# Sheet1.net
KiCad netlist of a schematic drawn in Altium Designer
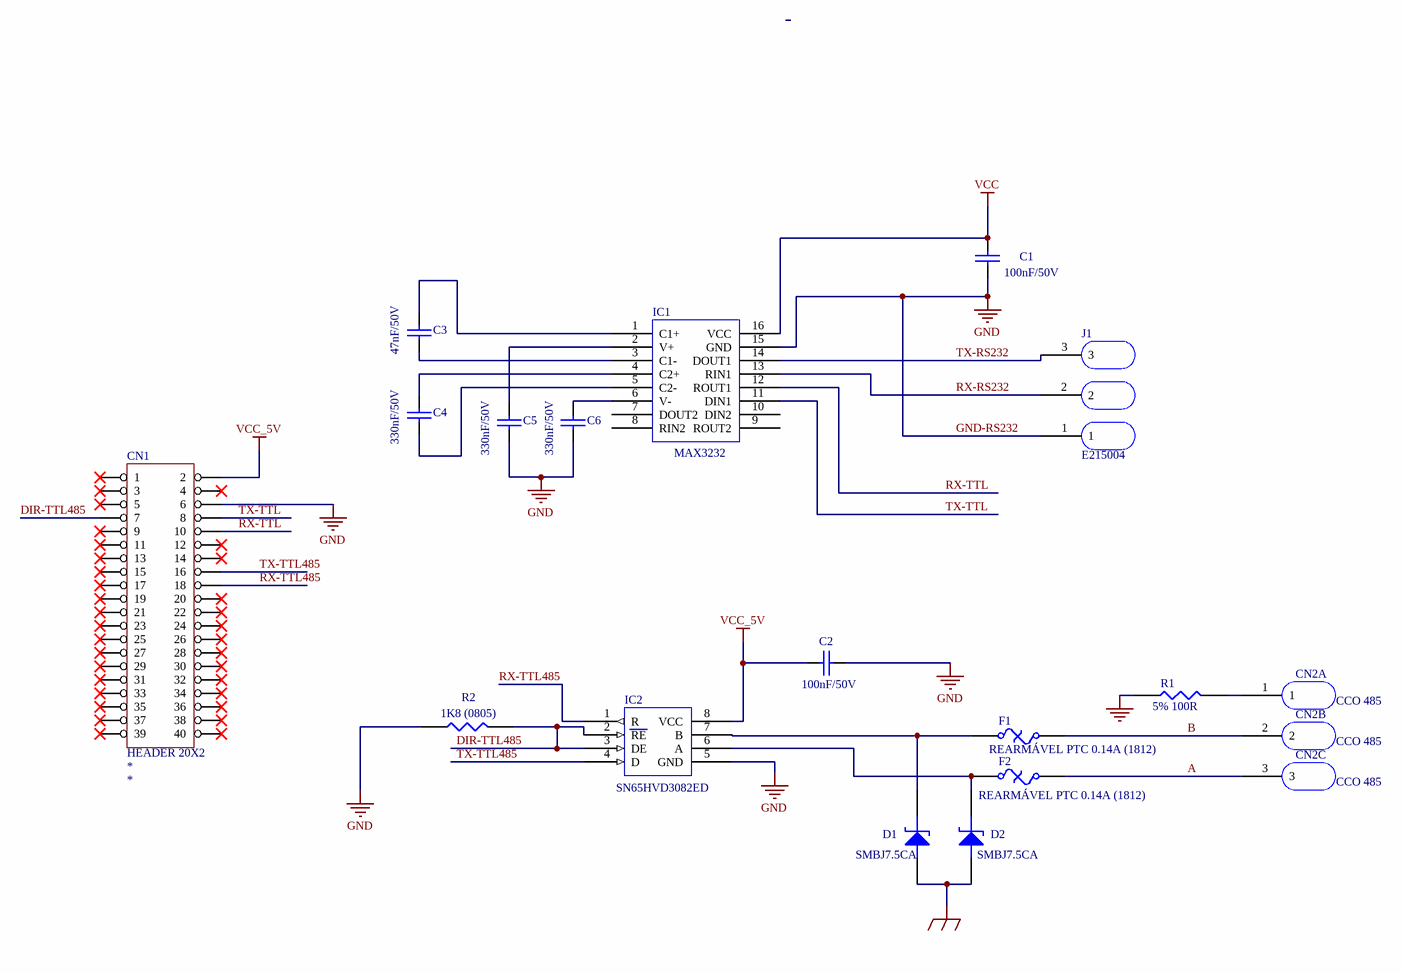
[diagram p0: Sheet1.SchDoc]

(export (version "E")
  (design (tool "Eeschema 10.0.6"))
  (components
    (comp (ref "C1")
      (value "B217602")
      (footprint "C0805")
      (description "COND. CERAMICO SMD 10% 100NF (0805) 50V")
      (fields (field (name "ALTIUM_UNNAMED_1") "100nF/50V"))
      (libsource (lib "LIBRARIAS_DMS_SCH") (part "CAP"))
    )
    (comp (ref "C2")
      (value "B217602")
      (footprint "C0805")
      (description "COND. CERAMICO SMD 10% 100NF (0805) 50V")
      (fields (field (name "ALTIUM_UNNAMED_1") "100nF/50V"))
      (libsource (lib "LIBRARIAS_DMS_SCH") (part "CAP"))
    )
    (comp (ref "C3")
      (value "B217602")
      (footprint "C0805")
      (description "COND. CERAMICO SMD 10% 100NF (0805) 50V")
      (fields (field (name "ALTIUM_UNNAMED_1") "47nF/50V"))
      (libsource (lib "LIBRARIAS_DMS_SCH") (part "CAP"))
    )
    (comp (ref "C4")
      (value "B217602")
      (footprint "C0805")
      (description "COND. CERAMICO SMD 10% 100NF (0805) 50V")
      (fields (field (name "ALTIUM_UNNAMED_1") "330nF/50V"))
      (libsource (lib "LIBRARIAS_DMS_SCH") (part "CAP"))
    )
    (comp (ref "C5")
      (value "B217602")
      (footprint "C0805")
      (description "COND. CERAMICO SMD 10% 100NF (0805) 50V")
      (fields (field (name "ALTIUM_UNNAMED_1") "330nF/50V"))
      (libsource (lib "LIBRARIAS_DMS_SCH") (part "CAP"))
    )
    (comp (ref "C6")
      (value "B217602")
      (footprint "C0805")
      (description "COND. CERAMICO SMD 10% 100NF (0805) 50V")
      (fields (field (name "ALTIUM_UNNAMED_1") "330nF/50V"))
      (libsource (lib "LIBRARIAS_DMS_SCH") (part "CAP"))
    )
    (comp (ref "CN1")
      (value "HEADER 20X2")
      (footprint "RÉGUA-40PINOS-A+B")
      (description "RÉGUA DE 40 PINOS MACHO 180G. 2X36P.")
      (fields (field (name "E215001") "*") (field (name "(2)") "*"))
      (libsource (lib "LIBRARIAS_DMS_SCH") (part "HEADER 20X2"))
    )
    (comp (ref "CN2")
      (value "CCO 485")
      (footprint "MOLEX-3PINOS-MACHO")
      (description "CONEC.MOLEX MACHO 6410-03A")
      (libsource (lib "*") (part "MOLEX MACHO 3 PINOS"))
    )
    (comp (ref "D1")
      (value "SMBJ7.5CA")
      (footprint "SMB (SMBJ7.5CA)")
      (description "DIODO SMD SMBJ7.5CA")
      (libsource (lib "*") (part "DIODO SMD SMBJ7.5CA"))
    )
    (comp (ref "D2")
      (value "SMBJ7.5CA")
      (footprint "SMB (SMBJ7.5CA)")
      (description "DIODO SMD SMBJ7.5CA")
      (libsource (lib "*") (part "DIODO SMD SMBJ7.5CA"))
    )
    (comp (ref "F1")
      (value "D616404")
      (footprint "1812")
      (description "FUSIVEL FUS.LENTA SMD REARMÁVEL PTC 0.14A (1812)")
      (fields (field (name "VALOR") "REARMÁVEL PTC 0.14A (1812)"))
      (libsource (lib "*") (part "Fuse Thermal"))
    )
    (comp (ref "F2")
      (value "D616404")
      (footprint "1812")
      (description "FUSIVEL FUS.LENTA SMD REARMÁVEL PTC 0.14A (1812)")
      (fields (field (name "VALOR") "REARMÁVEL PTC 0.14A (1812)"))
      (libsource (lib "*") (part "Fuse Thermal"))
    )
    (comp (ref "IC1")
      (value "MAX3232 (SOIC-16)")
      (footprint "LIBRARIAS MICRO_PCB:SOIC-16 (MAX3232)")
      (description "C.I. SMD MAX3232")
      (fields (field (name "VALOR") "MAX3232"))
      (libsource (lib "LIBRARIAS_DMS_SCH") (part "MAX3232 (SOIC-16)"))
    )
    (comp (ref "IC2")
      (value "SN65HVD3082")
      (footprint "LIBRARIAS MICRO_PCB_2009:PSOP-8")
      (description "INTEGRADO 8 PINOS SMD - SN65HVD3082ED")
      (fields (field (name "VALOR") "SN65HVD3082ED"))
      (libsource (lib "LIBRARIAS_DMS_SCH") (part "SN65HVD3082"))
    )
    (comp (ref "J1")
      (value "E215004")
      (footprint "REGUA 3 PINOS_DP2,54MM_FÊMEA")
      (description "CONECTOR MOLEX MACHO 6410-03A")
      (libsource (lib "LIBRARIAS_DMS_SCH") (part "3 PINOS ALIMENTA敲O"))
    )
    (comp (ref "R1")
      (value "B306009")
      (footprint "R0805")
      (description "RESISTÊNCIA SMD")
      (fields (field (name "VALOR") "5% 100R"))
      (libsource (lib "*") (part "RESISTENCIA SMD"))
    )
    (comp (ref "R2")
      (value "1K8 (0805)")
      (footprint "R0805")
      (description "RESISTENCIA SMD 5% 1K8 (0805)")
      (libsource (lib "LIBRARIAS_DMS_SCH") (part "RESISTENCIA SMD 5% 1K8 (0805)"))
    )
  )
  (nets
    (net (code "1") (name "/A") (class "Default")
      (node (ref "CN2") (pin "3") (pinfunction "3_3") (pintype "passive"))
      (node (ref "F2") (pin "2") (pinfunction "2_2") (pintype "passive"))
    )
    (net (code "2") (name "/B") (class "Default")
      (node (ref "CN2") (pin "2") (pinfunction "2_2") (pintype "passive"))
      (node (ref "F1") (pin "2") (pinfunction "2_2") (pintype "passive"))
    )
    (net (code "3") (name "/DIR-TTL485") (class "Default")
      (node (ref "CN1") (pin "7") (pinfunction "7_7") (pintype "passive"))
      (node (ref "IC2") (pin "2") (pinfunction "RE_2") (pintype "input"))
      (node (ref "IC2") (pin "3") (pinfunction "DE_3") (pintype "input"))
      (node (ref "R2") (pin "2") (pinfunction "2_2") (pintype "passive"))
    )
    (net (code "4") (name "/RX-RS232") (class "Default")
      (node (ref "IC1") (pin "13") (pinfunction "RIN1_13") (pintype "passive"))
      (node (ref "J1") (pin "2") (pinfunction "2_2") (pintype "passive"))
    )
    (net (code "5") (name "/RX-TTL") (class "Default")
      (node (ref "CN1") (pin "10") (pinfunction "10_10") (pintype "passive"))
      (node (ref "IC1") (pin "12") (pinfunction "ROUT1_12") (pintype "passive"))
    )
    (net (code "6") (name "/RX-TTL485") (class "Default")
      (node (ref "CN1") (pin "18") (pinfunction "18_18") (pintype "passive"))
      (node (ref "IC2") (pin "1") (pinfunction "R_1") (pintype "output"))
    )
    (net (code "7") (name "/TX-RS232") (class "Default")
      (node (ref "IC1") (pin "14") (pinfunction "DOUT1_14") (pintype "passive"))
      (node (ref "J1") (pin "3") (pinfunction "3_3") (pintype "passive"))
    )
    (net (code "8") (name "/TX-TTL") (class "Default")
      (node (ref "CN1") (pin "8") (pinfunction "8_8") (pintype "passive"))
      (node (ref "IC1") (pin "11") (pinfunction "DIN1_11") (pintype "passive"))
    )
    (net (code "9") (name "/TX-TTL485") (class "Default")
      (node (ref "CN1") (pin "16") (pinfunction "16_16") (pintype "passive"))
      (node (ref "IC2") (pin "4") (pinfunction "D_4") (pintype "input"))
    )
    (net (code "10") (name "EARTH") (class "Default")
      (node (ref "D1") (pin "2") (pinfunction "A_2") (pintype "passive"))
      (node (ref "D2") (pin "2") (pinfunction "A_2") (pintype "passive"))
    )
    (net (code "11") (name "GND") (class "Default")
      (node (ref "C1") (pin "2") (pinfunction "2_2") (pintype "passive"))
      (node (ref "C2") (pin "2") (pinfunction "2_2") (pintype "passive"))
      (node (ref "C5") (pin "2") (pinfunction "2_2") (pintype "passive"))
      (node (ref "C6") (pin "2") (pinfunction "2_2") (pintype "passive"))
      (node (ref "CN1") (pin "6") (pinfunction "6_6") (pintype "passive"))
      (node (ref "IC1") (pin "15") (pinfunction "GND_15") (pintype "power_in"))
      (node (ref "IC2") (pin "5") (pinfunction "GND_5") (pintype "power_in"))
      (node (ref "J1") (pin "1") (pinfunction "1_1") (pintype "passive"))
      (node (ref "R1") (pin "1") (pinfunction "1_1") (pintype "passive"))
      (node (ref "R2") (pin "1") (pinfunction "1_1") (pintype "passive"))
    )
    (net (code "12") (name "Net-(CN2-Pad1)") (class "Default")
      (node (ref "CN2") (pin "1") (pinfunction "1_1") (pintype "passive"))
      (node (ref "R1") (pin "2") (pinfunction "2_2") (pintype "passive"))
    )
    (net (code "13") (name "Net-(D1-K)") (class "Default")
      (node (ref "D1") (pin "1") (pinfunction "K_1") (pintype "passive"))
      (node (ref "F1") (pin "1") (pinfunction "1_1") (pintype "passive"))
      (node (ref "IC2") (pin "7") (pinfunction "B_7") (pintype "tri_state"))
    )
    (net (code "14") (name "Net-(D2-K)") (class "Default")
      (node (ref "D2") (pin "1") (pinfunction "K_1") (pintype "passive"))
      (node (ref "F2") (pin "1") (pinfunction "1_1") (pintype "passive"))
      (node (ref "IC2") (pin "6") (pinfunction "A_6") (pintype "tri_state"))
    )
    (net (code "15") (name "Net-(IC1-C1+)") (class "Default")
      (node (ref "C3") (pin "1") (pinfunction "1_1") (pintype "passive"))
      (node (ref "IC1") (pin "1") (pinfunction "C1+_1") (pintype "passive"))
    )
    (net (code "16") (name "Net-(IC1-C1-)") (class "Default")
      (node (ref "C3") (pin "2") (pinfunction "2_2") (pintype "passive"))
      (node (ref "IC1") (pin "3") (pinfunction "C1-_3") (pintype "passive"))
    )
    (net (code "17") (name "Net-(IC1-C2+)") (class "Default")
      (node (ref "C4") (pin "1") (pinfunction "1_1") (pintype "passive"))
      (node (ref "IC1") (pin "4") (pinfunction "C2+_4") (pintype "passive"))
    )
    (net (code "18") (name "Net-(IC1-C2-)") (class "Default")
      (node (ref "C4") (pin "2") (pinfunction "2_2") (pintype "passive"))
      (node (ref "IC1") (pin "5") (pinfunction "C2-_5") (pintype "passive"))
    )
    (net (code "19") (name "Net-(IC1-V+)") (class "Default")
      (node (ref "C5") (pin "1") (pinfunction "1_1") (pintype "passive"))
      (node (ref "IC1") (pin "2") (pinfunction "V+_2") (pintype "power_in"))
    )
    (net (code "20") (name "Net-(IC1-V-)") (class "Default")
      (node (ref "C6") (pin "1") (pinfunction "1_1") (pintype "passive"))
      (node (ref "IC1") (pin "6") (pinfunction "V-_6") (pintype "power_in"))
    )
    (net (code "21") (name "VCC") (class "Default")
      (node (ref "C1") (pin "1") (pinfunction "1_1") (pintype "passive"))
      (node (ref "IC1") (pin "16") (pinfunction "VCC_16") (pintype "power_in"))
    )
    (net (code "22") (name "VCC_5V") (class "Default")
      (node (ref "C2") (pin "1") (pinfunction "1_1") (pintype "passive"))
      (node (ref "CN1") (pin "2") (pinfunction "2_2") (pintype "passive"))
      (node (ref "IC2") (pin "8") (pinfunction "VCC_8") (pintype "power_in"))
    )
    (net (code "23") (name "unconnected-(CN1-Pad1)") (class "Default")
      (node (ref "CN1") (pin "1") (pinfunction "1_1") (pintype "passive+no_connect"))
    )
    (net (code "24") (name "unconnected-(CN1-Pad3)") (class "Default")
      (node (ref "CN1") (pin "3") (pinfunction "3_3") (pintype "passive+no_connect"))
    )
    (net (code "25") (name "unconnected-(CN1-Pad4)") (class "Default")
      (node (ref "CN1") (pin "4") (pinfunction "4_4") (pintype "passive+no_connect"))
    )
    (net (code "26") (name "unconnected-(CN1-Pad5)") (class "Default")
      (node (ref "CN1") (pin "5") (pinfunction "5_5") (pintype "passive+no_connect"))
    )
    (net (code "27") (name "unconnected-(CN1-Pad9)") (class "Default")
      (node (ref "CN1") (pin "9") (pinfunction "9_9") (pintype "passive+no_connect"))
    )
    (net (code "28") (name "unconnected-(CN1-Pad11)") (class "Default")
      (node (ref "CN1") (pin "11") (pinfunction "11_11") (pintype "passive+no_connect"))
    )
    (net (code "29") (name "unconnected-(CN1-Pad12)") (class "Default")
      (node (ref "CN1") (pin "12") (pinfunction "12_12") (pintype "passive+no_connect"))
    )
    (net (code "30") (name "unconnected-(CN1-Pad13)") (class "Default")
      (node (ref "CN1") (pin "13") (pinfunction "13_13") (pintype "passive+no_connect"))
    )
    (net (code "31") (name "unconnected-(CN1-Pad14)") (class "Default")
      (node (ref "CN1") (pin "14") (pinfunction "14_14") (pintype "passive+no_connect"))
    )
    (net (code "32") (name "unconnected-(CN1-Pad15)") (class "Default")
      (node (ref "CN1") (pin "15") (pinfunction "15_15") (pintype "passive+no_connect"))
    )
    (net (code "33") (name "unconnected-(CN1-Pad17)") (class "Default")
      (node (ref "CN1") (pin "17") (pinfunction "17_17") (pintype "passive+no_connect"))
    )
    (net (code "34") (name "unconnected-(CN1-Pad19)") (class "Default")
      (node (ref "CN1") (pin "19") (pinfunction "19_19") (pintype "passive+no_connect"))
    )
    (net (code "35") (name "unconnected-(CN1-Pad20)") (class "Default")
      (node (ref "CN1") (pin "20") (pinfunction "20_20") (pintype "passive+no_connect"))
    )
    (net (code "36") (name "unconnected-(CN1-Pad21)") (class "Default")
      (node (ref "CN1") (pin "21") (pinfunction "21_21") (pintype "passive+no_connect"))
    )
    (net (code "37") (name "unconnected-(CN1-Pad22)") (class "Default")
      (node (ref "CN1") (pin "22") (pinfunction "22_22") (pintype "passive+no_connect"))
    )
    (net (code "38") (name "unconnected-(CN1-Pad23)") (class "Default")
      (node (ref "CN1") (pin "23") (pinfunction "23_23") (pintype "passive+no_connect"))
    )
    (net (code "39") (name "unconnected-(CN1-Pad24)") (class "Default")
      (node (ref "CN1") (pin "24") (pinfunction "24_24") (pintype "passive+no_connect"))
    )
    (net (code "40") (name "unconnected-(CN1-Pad25)") (class "Default")
      (node (ref "CN1") (pin "25") (pinfunction "25_25") (pintype "passive+no_connect"))
    )
    (net (code "41") (name "unconnected-(CN1-Pad26)") (class "Default")
      (node (ref "CN1") (pin "26") (pinfunction "26_26") (pintype "passive+no_connect"))
    )
    (net (code "42") (name "unconnected-(CN1-Pad27)") (class "Default")
      (node (ref "CN1") (pin "27") (pinfunction "27_27") (pintype "passive+no_connect"))
    )
    (net (code "43") (name "unconnected-(CN1-Pad28)") (class "Default")
      (node (ref "CN1") (pin "28") (pinfunction "28_28") (pintype "passive+no_connect"))
    )
    (net (code "44") (name "unconnected-(CN1-Pad29)") (class "Default")
      (node (ref "CN1") (pin "29") (pinfunction "29_29") (pintype "passive+no_connect"))
    )
    (net (code "45") (name "unconnected-(CN1-Pad30)") (class "Default")
      (node (ref "CN1") (pin "30") (pinfunction "30_30") (pintype "passive+no_connect"))
    )
    (net (code "46") (name "unconnected-(CN1-Pad31)") (class "Default")
      (node (ref "CN1") (pin "31") (pinfunction "31_31") (pintype "passive+no_connect"))
    )
    (net (code "47") (name "unconnected-(CN1-Pad32)") (class "Default")
      (node (ref "CN1") (pin "32") (pinfunction "32_32") (pintype "passive+no_connect"))
    )
    (net (code "48") (name "unconnected-(CN1-Pad33)") (class "Default")
      (node (ref "CN1") (pin "33") (pinfunction "33_33") (pintype "passive+no_connect"))
    )
    (net (code "49") (name "unconnected-(CN1-Pad34)") (class "Default")
      (node (ref "CN1") (pin "34") (pinfunction "34_34") (pintype "passive+no_connect"))
    )
    (net (code "50") (name "unconnected-(CN1-Pad35)") (class "Default")
      (node (ref "CN1") (pin "35") (pinfunction "35_35") (pintype "passive+no_connect"))
    )
    (net (code "51") (name "unconnected-(CN1-Pad36)") (class "Default")
      (node (ref "CN1") (pin "36") (pinfunction "36_36") (pintype "passive+no_connect"))
    )
    (net (code "52") (name "unconnected-(CN1-Pad37)") (class "Default")
      (node (ref "CN1") (pin "37") (pinfunction "37_37") (pintype "passive+no_connect"))
    )
    (net (code "53") (name "unconnected-(CN1-Pad38)") (class "Default")
      (node (ref "CN1") (pin "38") (pinfunction "38_38") (pintype "passive+no_connect"))
    )
    (net (code "54") (name "unconnected-(CN1-Pad39)") (class "Default")
      (node (ref "CN1") (pin "39") (pinfunction "39_39") (pintype "passive+no_connect"))
    )
    (net (code "55") (name "unconnected-(CN1-Pad40)") (class "Default")
      (node (ref "CN1") (pin "40") (pinfunction "40_40") (pintype "passive+no_connect"))
    )
    (net (code "56") (name "unconnected-(IC1-DIN2-Pad10)") (class "Default")
      (node (ref "IC1") (pin "10") (pinfunction "DIN2_10") (pintype "passive"))
    )
    (net (code "57") (name "unconnected-(IC1-DOUT2-Pad7)") (class "Default")
      (node (ref "IC1") (pin "7") (pinfunction "DOUT2_7") (pintype "passive"))
    )
    (net (code "58") (name "unconnected-(IC1-RIN2-Pad8)") (class "Default")
      (node (ref "IC1") (pin "8") (pinfunction "RIN2_8") (pintype "passive"))
    )
    (net (code "59") (name "unconnected-(IC1-ROUT2-Pad9)") (class "Default")
      (node (ref "IC1") (pin "9") (pinfunction "ROUT2_9") (pintype "passive"))
    )
  )
)
